# Shield_Motor_DIP.net
KiCad netlist of a schematic drawn in EAGLE
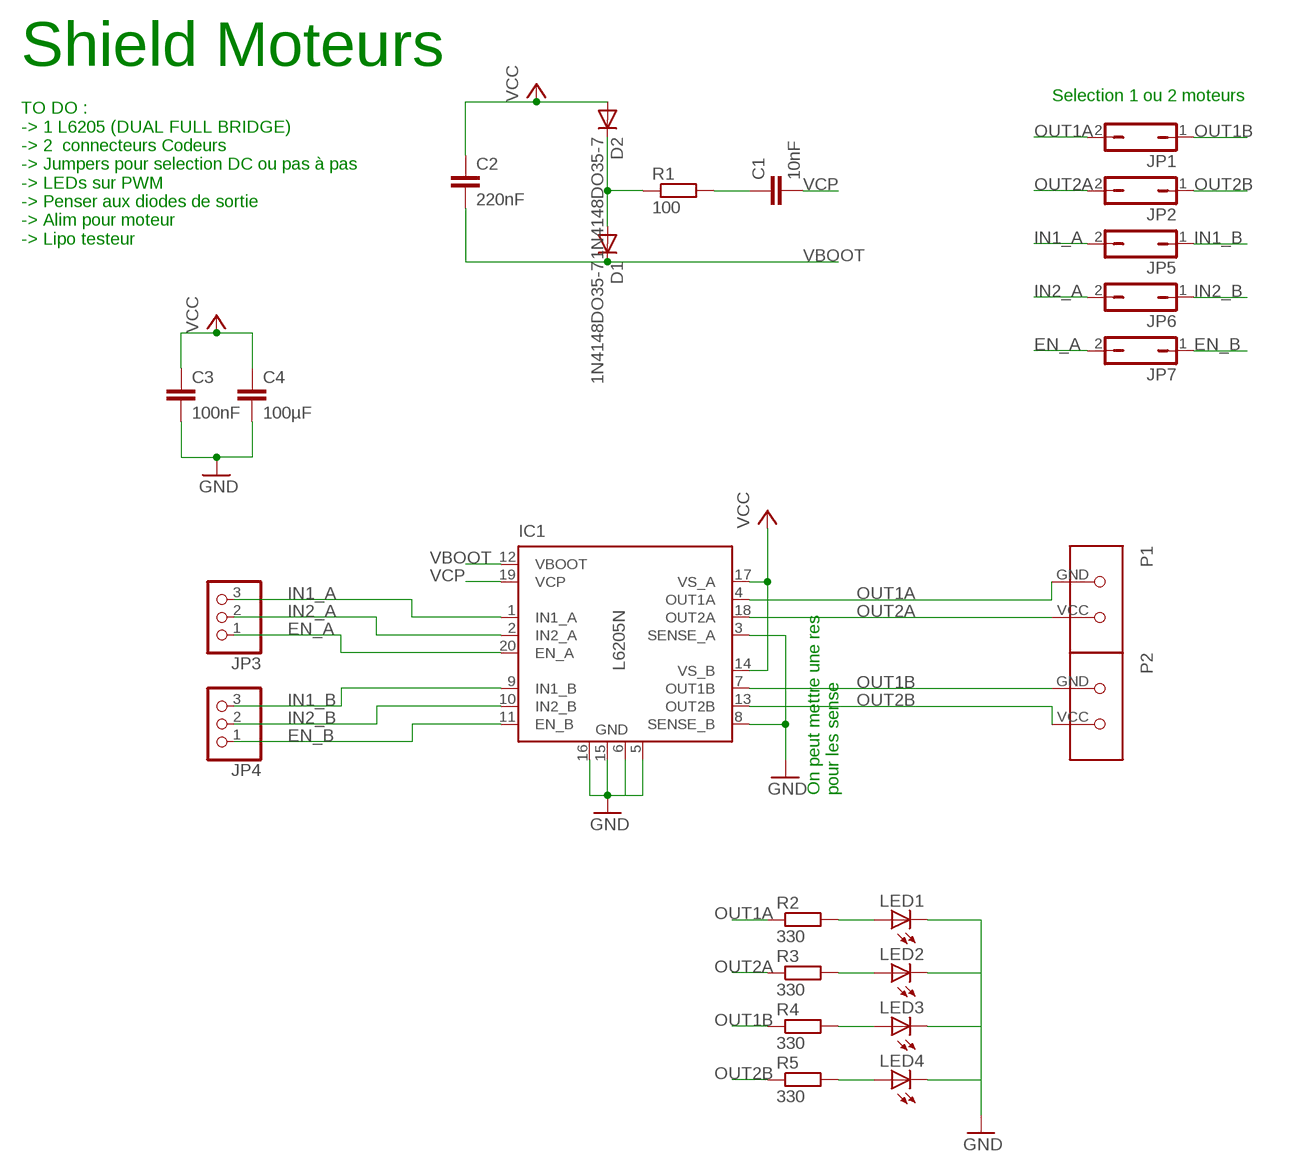
[diagram p0: schematic, sheet 1]

(export (version "E")
  (design (tool "Eeschema 10.0.6"))
  (components
    (comp (ref "C1")
      (value "10nF")
      (footprint "eagle-import:C050-035X075")
      (libsource (lib "eagle-import") (part "C-EU050-035X075"))
    )
    (comp (ref "C2")
      (value "220nF")
      (footprint "eagle-import:C050-035X075")
      (libsource (lib "eagle-import") (part "C-EU050-035X075"))
    )
    (comp (ref "C3")
      (value "100nF")
      (footprint "eagle-import:C050-035X075")
      (libsource (lib "eagle-import") (part "C-EU050-035X075"))
    )
    (comp (ref "C4")
      (value "100µF")
      (footprint "eagle-import:C050-035X075")
      (libsource (lib "eagle-import") (part "C-EU050-035X075"))
    )
    (comp (ref "D1")
      (value "1N4148DO35-7")
      (footprint "eagle-import:DO35-7")
      (libsource (lib "eagle-import") (part "1N4148DO35-7"))
    )
    (comp (ref "D2")
      (value "1N4148DO35-7")
      (footprint "eagle-import:DO35-7")
      (libsource (lib "eagle-import") (part "1N4148DO35-7"))
    )
    (comp (ref "IC1")
      (value "L6205N")
      (footprint "eagle-import:DIL20")
      (fields (field (name "MF") "Arrow Electronics"))
      (libsource (lib "eagle-import") (part "L6205N"))
    )
    (comp (ref "JP1")
      (value "JP1Q")
      (footprint "eagle-import:JP1")
      (libsource (lib "eagle-import") (part "JP1Q"))
    )
    (comp (ref "JP2")
      (value "JP1Q")
      (footprint "eagle-import:JP1")
      (libsource (lib "eagle-import") (part "JP1Q"))
    )
    (comp (ref "JP3")
      (value "PINHD-1X3")
      (footprint "eagle-import:1X03")
      (libsource (lib "eagle-import") (part "PINHD-1X3"))
    )
    (comp (ref "JP4")
      (value "PINHD-1X3")
      (footprint "eagle-import:1X03")
      (libsource (lib "eagle-import") (part "PINHD-1X3"))
    )
    (comp (ref "JP5")
      (value "JP1Q")
      (footprint "eagle-import:JP1")
      (libsource (lib "eagle-import") (part "JP1Q"))
    )
    (comp (ref "JP6")
      (value "JP1Q")
      (footprint "eagle-import:JP1")
      (libsource (lib "eagle-import") (part "JP1Q"))
    )
    (comp (ref "JP7")
      (value "JP1Q")
      (footprint "eagle-import:JP1")
      (libsource (lib "eagle-import") (part "JP1Q"))
    )
    (comp (ref "LED1")
      (value "LED3MM")
      (footprint "eagle-import:LED3MM")
      (libsource (lib "eagle-import") (part "LED3MM"))
    )
    (comp (ref "LED2")
      (value "LED3MM")
      (footprint "eagle-import:LED3MM")
      (libsource (lib "eagle-import") (part "LED3MM"))
    )
    (comp (ref "LED3")
      (value "LED3MM")
      (footprint "eagle-import:LED3MM")
      (libsource (lib "eagle-import") (part "LED3MM"))
    )
    (comp (ref "LED4")
      (value "LED3MM")
      (footprint "eagle-import:LED3MM")
      (libsource (lib "eagle-import") (part "LED3MM"))
    )
    (comp (ref "P1")
      (value "BORNIER_3.5MM")
      (footprint "eagle-import:BORNIER_COUDEE_3.5")
      (libsource (lib "eagle-import") (part "BORNIER_3.5MM"))
    )
    (comp (ref "P2")
      (value "BORNIER_3.5MM")
      (footprint "eagle-import:BORNIER_COUDEE_3.5")
      (libsource (lib "eagle-import") (part "BORNIER_3.5MM"))
    )
    (comp (ref "R1")
      (value "100")
      (footprint "eagle-import:0204_7")
      (libsource (lib "eagle-import") (part "R-EU_0204/7"))
    )
    (comp (ref "R2")
      (value "330")
      (footprint "eagle-import:0204_7")
      (libsource (lib "eagle-import") (part "R-EU_0204/7"))
    )
    (comp (ref "R3")
      (value "330")
      (footprint "eagle-import:0204_7")
      (libsource (lib "eagle-import") (part "R-EU_0204/7"))
    )
    (comp (ref "R4")
      (value "330")
      (footprint "eagle-import:0204_7")
      (libsource (lib "eagle-import") (part "R-EU_0204/7"))
    )
    (comp (ref "R5")
      (value "330")
      (footprint "eagle-import:0204_7")
      (libsource (lib "eagle-import") (part "R-EU_0204/7"))
    )
  )
  (nets
    (net (code "1") (name "/EN_A") (class "Default")
      (node (ref "IC1") (pin "20") (pinfunction "EN_A_20") (pintype "input"))
      (node (ref "JP3") (pin "1") (pinfunction "1_1") (pintype "passive"))
      (node (ref "JP7") (pin "2") (pinfunction "2_2") (pintype "passive"))
    )
    (net (code "2") (name "/EN_B") (class "Default")
      (node (ref "IC1") (pin "11") (pinfunction "EN_B_11") (pintype "input"))
      (node (ref "JP4") (pin "1") (pinfunction "1_1") (pintype "passive"))
      (node (ref "JP7") (pin "1") (pinfunction "1_1") (pintype "passive"))
    )
    (net (code "3") (name "/IN1_A") (class "Default")
      (node (ref "IC1") (pin "1") (pinfunction "IN1_A_1") (pintype "input"))
      (node (ref "JP3") (pin "3") (pinfunction "3_3") (pintype "passive"))
      (node (ref "JP5") (pin "2") (pinfunction "2_2") (pintype "passive"))
    )
    (net (code "4") (name "/IN1_B") (class "Default")
      (node (ref "IC1") (pin "9") (pinfunction "IN1_B_9") (pintype "input"))
      (node (ref "JP4") (pin "3") (pinfunction "3_3") (pintype "passive"))
      (node (ref "JP5") (pin "1") (pinfunction "1_1") (pintype "passive"))
    )
    (net (code "5") (name "/IN2_A") (class "Default")
      (node (ref "IC1") (pin "2") (pinfunction "IN2_A_2") (pintype "input"))
      (node (ref "JP3") (pin "2") (pinfunction "2_2") (pintype "passive"))
      (node (ref "JP6") (pin "2") (pinfunction "2_2") (pintype "passive"))
    )
    (net (code "6") (name "/IN2_B") (class "Default")
      (node (ref "IC1") (pin "10") (pinfunction "IN2_B_10") (pintype "input"))
      (node (ref "JP4") (pin "2") (pinfunction "2_2") (pintype "passive"))
      (node (ref "JP6") (pin "1") (pinfunction "1_1") (pintype "passive"))
    )
    (net (code "7") (name "/OUT1A") (class "Default")
      (node (ref "IC1") (pin "4") (pinfunction "OUT1A_4") (pintype "output"))
      (node (ref "JP1") (pin "2") (pinfunction "2_2") (pintype "passive"))
      (node (ref "P1") (pin "GND") (pinfunction "GND_GND") (pintype "bidirectional"))
      (node (ref "R2") (pin "1") (pinfunction "1_1") (pintype "passive"))
    )
    (net (code "8") (name "/OUT1B") (class "Default")
      (node (ref "IC1") (pin "7") (pinfunction "OUT1B_7") (pintype "output"))
      (node (ref "JP1") (pin "1") (pinfunction "1_1") (pintype "passive"))
      (node (ref "P2") (pin "GND") (pinfunction "GND_GND") (pintype "bidirectional"))
      (node (ref "R4") (pin "1") (pinfunction "1_1") (pintype "passive"))
    )
    (net (code "9") (name "/OUT2A") (class "Default")
      (node (ref "IC1") (pin "18") (pinfunction "OUT2A_18") (pintype "output"))
      (node (ref "JP2") (pin "2") (pinfunction "2_2") (pintype "passive"))
      (node (ref "P1") (pin "VCC") (pinfunction "VCC_VCC") (pintype "bidirectional"))
      (node (ref "R3") (pin "1") (pinfunction "1_1") (pintype "passive"))
    )
    (net (code "10") (name "/OUT2B") (class "Default")
      (node (ref "IC1") (pin "13") (pinfunction "OUT2B_13") (pintype "output"))
      (node (ref "JP2") (pin "1") (pinfunction "1_1") (pintype "passive"))
      (node (ref "P2") (pin "VCC") (pinfunction "VCC_VCC") (pintype "bidirectional"))
      (node (ref "R5") (pin "1") (pinfunction "1_1") (pintype "passive"))
    )
    (net (code "11") (name "/VBOOT") (class "Default")
      (node (ref "C2") (pin "2") (pinfunction "2_2") (pintype "passive"))
      (node (ref "D1") (pin "C") (pinfunction "C_C") (pintype "passive"))
      (node (ref "IC1") (pin "12") (pinfunction "VBOOT_12") (pintype "power_in"))
    )
    (net (code "12") (name "/VCP") (class "Default")
      (node (ref "C1") (pin "2") (pinfunction "2_2") (pintype "passive"))
      (node (ref "IC1") (pin "19") (pinfunction "VCP_19") (pintype "power_in"))
    )
    (net (code "13") (name "GND") (class "Default")
      (node (ref "C3") (pin "2") (pinfunction "2_2") (pintype "passive"))
      (node (ref "C4") (pin "2") (pinfunction "2_2") (pintype "passive"))
      (node (ref "IC1") (pin "15") (pinfunction "GND_15") (pintype "power_in"))
      (node (ref "IC1") (pin "16") (pinfunction "GND_16") (pintype "power_in"))
      (node (ref "IC1") (pin "3") (pinfunction "SENSE_A_3") (pintype "input"))
      (node (ref "IC1") (pin "5") (pinfunction "GND_5") (pintype "power_in"))
      (node (ref "IC1") (pin "6") (pinfunction "GND_6") (pintype "power_in"))
      (node (ref "IC1") (pin "8") (pinfunction "SENSE_B_8") (pintype "input"))
      (node (ref "LED1") (pin "K") (pinfunction "C_K") (pintype "passive"))
      (node (ref "LED2") (pin "K") (pinfunction "C_K") (pintype "passive"))
      (node (ref "LED3") (pin "K") (pinfunction "C_K") (pintype "passive"))
      (node (ref "LED4") (pin "K") (pinfunction "C_K") (pintype "passive"))
    )
    (net (code "14") (name "Net-(C1-Pad1)") (class "Default")
      (node (ref "C1") (pin "1") (pinfunction "1_1") (pintype "passive"))
      (node (ref "R1") (pin "2") (pinfunction "2_2") (pintype "passive"))
    )
    (net (code "15") (name "Net-(D1-PadA)") (class "Default")
      (node (ref "D1") (pin "A") (pinfunction "A_A") (pintype "passive"))
      (node (ref "D2") (pin "C") (pinfunction "C_C") (pintype "passive"))
      (node (ref "R1") (pin "1") (pinfunction "1_1") (pintype "passive"))
    )
    (net (code "16") (name "Net-(LED1-PadA)") (class "Default")
      (node (ref "LED1") (pin "A") (pinfunction "A_A") (pintype "passive"))
      (node (ref "R2") (pin "2") (pinfunction "2_2") (pintype "passive"))
    )
    (net (code "17") (name "Net-(LED2-PadA)") (class "Default")
      (node (ref "LED2") (pin "A") (pinfunction "A_A") (pintype "passive"))
      (node (ref "R3") (pin "2") (pinfunction "2_2") (pintype "passive"))
    )
    (net (code "18") (name "Net-(LED3-PadA)") (class "Default")
      (node (ref "LED3") (pin "A") (pinfunction "A_A") (pintype "passive"))
      (node (ref "R4") (pin "2") (pinfunction "2_2") (pintype "passive"))
    )
    (net (code "19") (name "Net-(LED4-PadA)") (class "Default")
      (node (ref "LED4") (pin "A") (pinfunction "A_A") (pintype "passive"))
      (node (ref "R5") (pin "2") (pinfunction "2_2") (pintype "passive"))
    )
    (net (code "20") (name "VCC") (class "Default")
      (node (ref "C2") (pin "1") (pinfunction "1_1") (pintype "passive"))
      (node (ref "C3") (pin "1") (pinfunction "1_1") (pintype "passive"))
      (node (ref "C4") (pin "1") (pinfunction "1_1") (pintype "passive"))
      (node (ref "D2") (pin "A") (pinfunction "A_A") (pintype "passive"))
      (node (ref "IC1") (pin "14") (pinfunction "VS_B_14") (pintype "power_in"))
      (node (ref "IC1") (pin "17") (pinfunction "VS_A_17") (pintype "power_in"))
    )
  )
)
